# can.net
KiCad netlist of a schematic drawn in Altium Designer
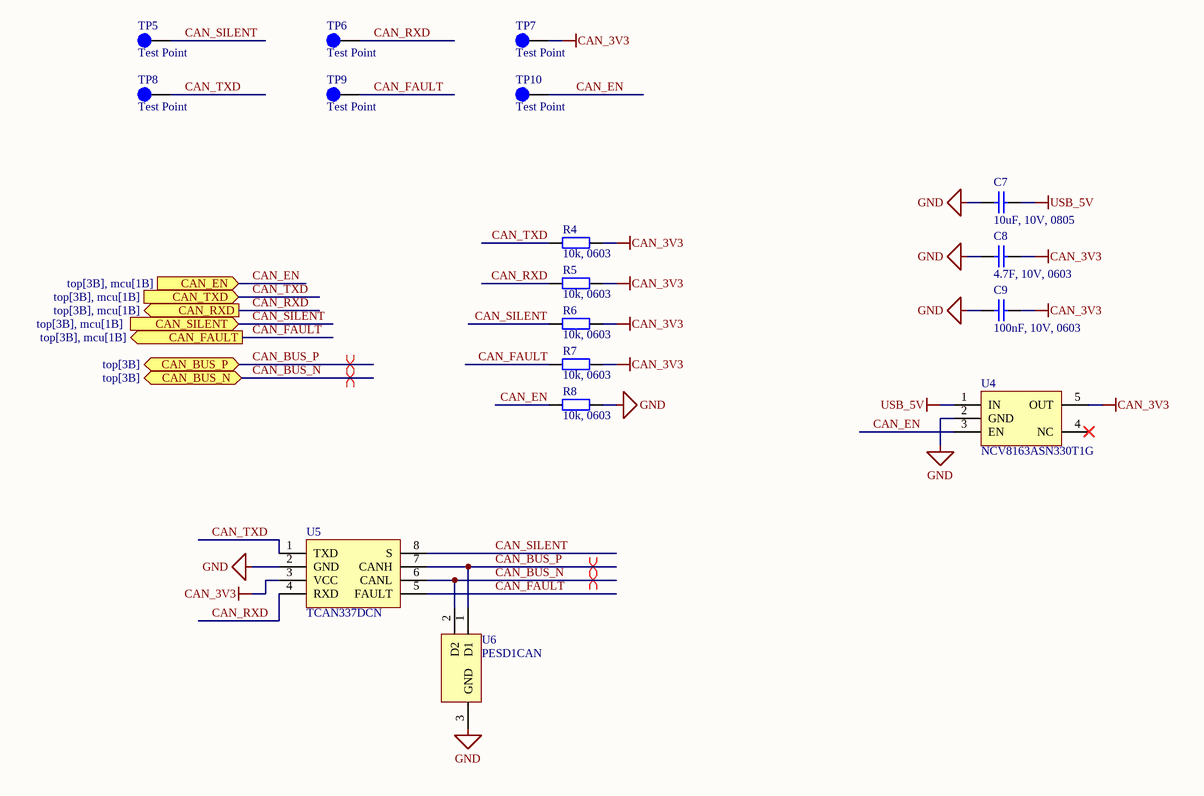
[diagram p0: can.SchDoc]

(export (version "E")
  (design (tool "Eeschema 10.0.6"))
  (components
    (comp (ref "C7")
      (value "10uF, 10V, 0805")
      (footprint "GENERIC_MLCC_CAP_0805_IPC_MEDIUM_DENSITY")
      (description "generic non-polarised capacitor")
      (libsource (lib "generic_passives") (part "Generic Non-polarised Capacitor"))
    )
    (comp (ref "C8")
      (value "4.7F, 10V, 0603")
      (footprint "GENERIC_MLCC_CAP_0603_IPC_MEDIUM_DENSITY")
      (description "generic non-polarised capacitor")
      (libsource (lib "generic_passives") (part "Generic Non-polarised Capacitor"))
    )
    (comp (ref "C9")
      (value "100nF, 10V, 0603")
      (footprint "GENERIC_MLCC_CAP_0603_IPC_MEDIUM_DENSITY")
      (description "generic non-polarised capacitor")
      (libsource (lib "generic_passives") (part "Generic Non-polarised Capacitor"))
    )
    (comp (ref "R4")
      (value "10k, 0603")
      (footprint "GENERIC_CHIP_RES_0603_IPC_MEDIUM_DENSITY")
      (description "generic resistor")
      (libsource (lib "generic_passives") (part "Generic Resistor"))
    )
    (comp (ref "R5")
      (value "10k, 0603")
      (footprint "GENERIC_CHIP_RES_0603_IPC_MEDIUM_DENSITY")
      (description "generic resistor")
      (libsource (lib "generic_passives") (part "Generic Resistor"))
    )
    (comp (ref "R6")
      (value "10k, 0603")
      (footprint "GENERIC_CHIP_RES_0603_IPC_MEDIUM_DENSITY")
      (description "generic resistor")
      (libsource (lib "generic_passives") (part "Generic Resistor"))
    )
    (comp (ref "R7")
      (value "10k, 0603")
      (footprint "GENERIC_CHIP_RES_0603_IPC_MEDIUM_DENSITY")
      (description "generic resistor")
      (libsource (lib "generic_passives") (part "Generic Resistor"))
    )
    (comp (ref "R8")
      (value "10k, 0603")
      (footprint "GENERIC_CHIP_RES_0603_IPC_MEDIUM_DENSITY")
      (description "generic resistor")
      (libsource (lib "generic_passives") (part "Generic Resistor"))
    )
    (comp (ref "TP5")
      (value "Test Point")
      (footprint "TEST_POINT_CIRCLE_1MM")
      (description "generic test point")
      (fields (field (name "PART NUMBER") "Test Point"))
      (libsource (lib "features") (part "Test Point"))
    )
    (comp (ref "TP6")
      (value "Test Point")
      (footprint "TEST_POINT_CIRCLE_1MM")
      (description "generic test point")
      (fields (field (name "PART NUMBER") "Test Point"))
      (libsource (lib "features") (part "Test Point"))
    )
    (comp (ref "TP7")
      (value "Test Point")
      (footprint "TEST_POINT_CIRCLE_1MM")
      (description "generic test point")
      (fields (field (name "PART NUMBER") "Test Point"))
      (libsource (lib "features") (part "Test Point"))
    )
    (comp (ref "TP8")
      (value "Test Point")
      (footprint "TEST_POINT_CIRCLE_1MM")
      (description "generic test point")
      (fields (field (name "PART NUMBER") "Test Point"))
      (libsource (lib "features") (part "Test Point"))
    )
    (comp (ref "TP9")
      (value "Test Point")
      (footprint "TEST_POINT_CIRCLE_1MM")
      (description "generic test point")
      (fields (field (name "PART NUMBER") "Test Point"))
      (libsource (lib "features") (part "Test Point"))
    )
    (comp (ref "TP10")
      (value "Test Point")
      (footprint "TEST_POINT_CIRCLE_1MM")
      (description "generic test point")
      (fields (field (name "PART NUMBER") "Test Point"))
      (libsource (lib "features") (part "Test Point"))
    )
    (comp (ref "U4")
      (value "NCV8163ASN330T1G")
      (footprint "NCV8163ASN330T1G_TSOP5")
      (description "3V3 250 mA LDO")
      (fields (field (name "MANUFACTURER") "Onsemi"))
      (libsource (lib "ldos") (part "NCV8163ASN330T1G"))
    )
    (comp (ref "U5")
      (value "TCAN337DCN")
      (footprint "can_bus_ics:TCAN337DCN_SOT23_8")
      (description "Texas Instruments 3.3-V CAN transceiver with CAN FD support. SOT-32 package.")
      (fields (field (name "MANUFACTURER") "Texas Instruments"))
      (libsource (lib "can_bus_ics") (part "TCAN337DCN"))
    )
    (comp (ref "U6")
      (value "PESD1CAN")
      (footprint "can_bus_ics:PESD1CAN_SOT23_3")
      (description "CAN bus ESD protection diode")
      (fields (field (name "MANUFACTURER") "Nexperia"))
      (libsource (lib "can_bus_ics") (part "PESD1CAN"))
    )
  )
  (nets
    (net (code "1") (name "/CAN_BUS_N") (class "Default")
      (node (ref "U5") (pin "6") (pinfunction "CANL_6") (pintype "passive"))
      (node (ref "U6") (pin "2") (pinfunction "D2_2") (pintype "passive"))
    )
    (net (code "2") (name "/CAN_BUS_P") (class "Default")
      (node (ref "U5") (pin "7") (pinfunction "CANH_7") (pintype "passive"))
      (node (ref "U6") (pin "1") (pinfunction "D1_1") (pintype "passive"))
    )
    (net (code "3") (name "/CAN_EN") (class "Default")
      (node (ref "R8") (pin "1") (pinfunction "1_1") (pintype "passive"))
      (node (ref "TP10") (pin "1") (pinfunction "TP_1") (pintype "passive"))
      (node (ref "U4") (pin "3") (pinfunction "EN_3") (pintype "passive"))
    )
    (net (code "4") (name "/CAN_FAULT") (class "Default")
      (node (ref "R7") (pin "1") (pinfunction "1_1") (pintype "passive"))
      (node (ref "TP9") (pin "1") (pinfunction "TP_1") (pintype "passive"))
      (node (ref "U5") (pin "5") (pinfunction "FAULT_5") (pintype "passive"))
    )
    (net (code "5") (name "/CAN_RXD") (class "Default")
      (node (ref "R5") (pin "1") (pinfunction "1_1") (pintype "passive"))
      (node (ref "TP6") (pin "1") (pinfunction "TP_1") (pintype "passive"))
      (node (ref "U5") (pin "4") (pinfunction "RXD_4") (pintype "passive"))
    )
    (net (code "6") (name "/CAN_SILENT") (class "Default")
      (node (ref "R6") (pin "1") (pinfunction "1_1") (pintype "passive"))
      (node (ref "TP5") (pin "1") (pinfunction "TP_1") (pintype "passive"))
      (node (ref "U5") (pin "8") (pinfunction "S_8") (pintype "passive"))
    )
    (net (code "7") (name "/CAN_TXD") (class "Default")
      (node (ref "R4") (pin "1") (pinfunction "1_1") (pintype "passive"))
      (node (ref "TP8") (pin "1") (pinfunction "TP_1") (pintype "passive"))
      (node (ref "U5") (pin "1") (pinfunction "TXD_1") (pintype "passive"))
    )
    (net (code "8") (name "CAN_3V3") (class "Default")
      (node (ref "C8") (pin "2") (pinfunction "2_2") (pintype "passive"))
      (node (ref "C9") (pin "2") (pinfunction "2_2") (pintype "passive"))
      (node (ref "R4") (pin "2") (pinfunction "2_2") (pintype "passive"))
      (node (ref "R5") (pin "2") (pinfunction "2_2") (pintype "passive"))
      (node (ref "R6") (pin "2") (pinfunction "2_2") (pintype "passive"))
      (node (ref "R7") (pin "2") (pinfunction "2_2") (pintype "passive"))
      (node (ref "TP7") (pin "1") (pinfunction "TP_1") (pintype "passive"))
      (node (ref "U4") (pin "5") (pinfunction "OUT_5") (pintype "passive"))
      (node (ref "U5") (pin "3") (pinfunction "VCC_3") (pintype "passive"))
    )
    (net (code "9") (name "GND") (class "Default")
      (node (ref "C7") (pin "1") (pinfunction "1_1") (pintype "passive"))
      (node (ref "C8") (pin "1") (pinfunction "1_1") (pintype "passive"))
      (node (ref "C9") (pin "1") (pinfunction "1_1") (pintype "passive"))
      (node (ref "R8") (pin "2") (pinfunction "2_2") (pintype "passive"))
      (node (ref "U4") (pin "2") (pinfunction "GND_2") (pintype "passive"))
      (node (ref "U5") (pin "2") (pinfunction "GND_2") (pintype "passive"))
      (node (ref "U6") (pin "3") (pinfunction "GND_3") (pintype "passive"))
    )
    (net (code "10") (name "USB_5V") (class "Default")
      (node (ref "C7") (pin "2") (pinfunction "2_2") (pintype "passive"))
      (node (ref "U4") (pin "1") (pinfunction "IN_1") (pintype "passive"))
    )
    (net (code "11") (name "unconnected-(U4-NC-Pad4)") (class "Default")
      (node (ref "U4") (pin "4") (pinfunction "NC_4") (pintype "passive+no_connect"))
    )
  )
)
